# fpa-sao.net
KiCad netlist of a schematic drawn in EAGLE
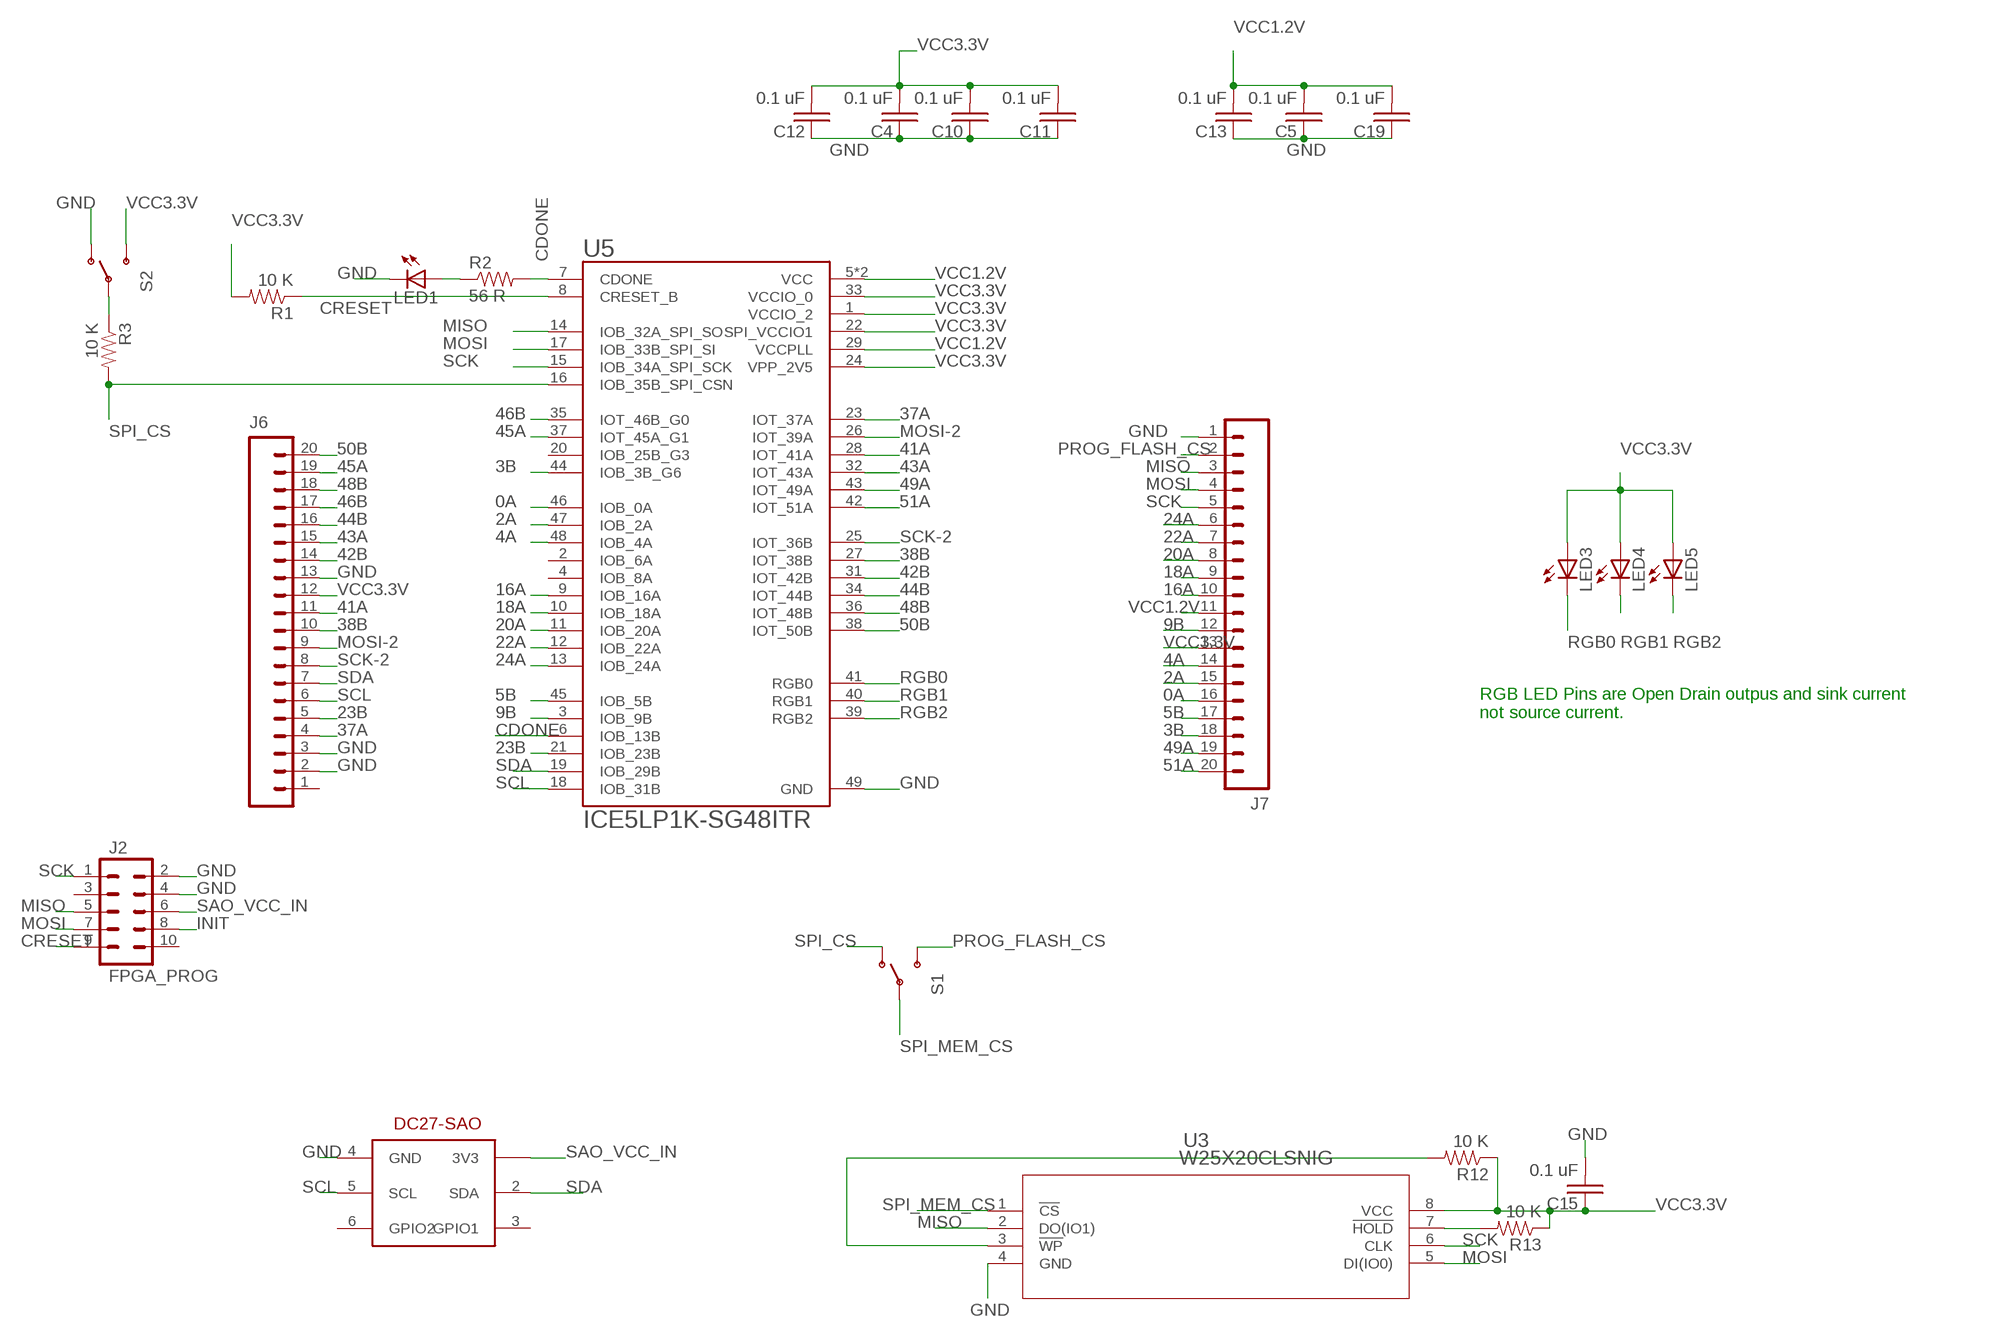
[diagram p0: schematic, sheet 1]
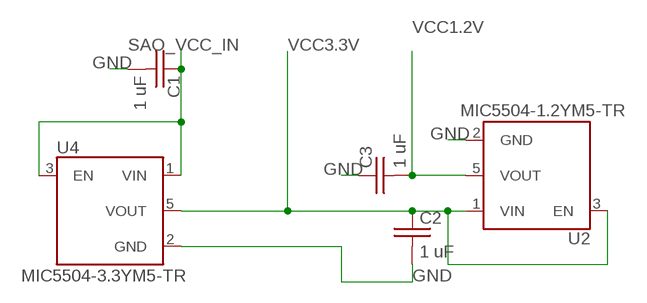
[diagram p1: schematic, sheet 2]
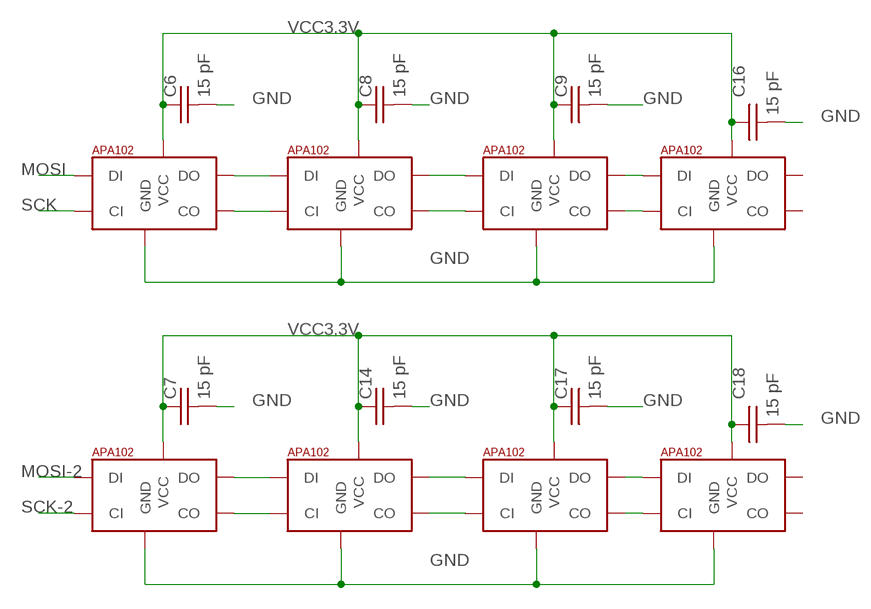
[diagram p2: schematic, sheet 3]
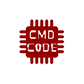
[diagram p3: schematic, sheet 4]

(export (version "E")
  (design (tool "Eeschema 10.0.6"))
  (components
    (comp (ref "C6")
      (value "15 pF")
      (footprint "eagle-import:C1206")
      (libsource (lib "eagle-import") (part "C-USC1206"))
    )
    (comp (ref "C7")
      (value "15 pF")
      (footprint "eagle-import:C1206")
      (libsource (lib "eagle-import") (part "C-USC1206"))
    )
    (comp (ref "C8")
      (value "15 pF")
      (footprint "eagle-import:C1206")
      (libsource (lib "eagle-import") (part "C-USC1206"))
    )
    (comp (ref "C9")
      (value "15 pF")
      (footprint "eagle-import:C1206")
      (libsource (lib "eagle-import") (part "C-USC1206"))
    )
    (comp (ref "C14")
      (value "15 pF")
      (footprint "eagle-import:C1206")
      (libsource (lib "eagle-import") (part "C-USC1206"))
    )
    (comp (ref "C16")
      (value "15 pF")
      (footprint "eagle-import:C1206")
      (libsource (lib "eagle-import") (part "C-USC1206"))
    )
    (comp (ref "C17")
      (value "15 pF")
      (footprint "eagle-import:C1206")
      (libsource (lib "eagle-import") (part "C-USC1206"))
    )
    (comp (ref "C18")
      (value "15 pF")
      (footprint "eagle-import:C1206")
      (libsource (lib "eagle-import") (part "C-USC1206"))
    )
    (comp (ref "U$2")
      (value "APA1025050")
      (footprint "eagle-import:APA102_5050")
      (libsource (lib "eagle-import") (part "APA1025050"))
    )
    (comp (ref "U$3")
      (value "APA1025050")
      (footprint "eagle-import:APA102_5050")
      (libsource (lib "eagle-import") (part "APA1025050"))
    )
    (comp (ref "U$4")
      (value "APA1025050")
      (footprint "eagle-import:APA102_5050")
      (libsource (lib "eagle-import") (part "APA1025050"))
    )
    (comp (ref "U$5")
      (value "APA1025050")
      (footprint "eagle-import:APA102_5050")
      (libsource (lib "eagle-import") (part "APA1025050"))
    )
    (comp (ref "U$6")
      (value "APA1025050")
      (footprint "eagle-import:APA102_5050")
      (libsource (lib "eagle-import") (part "APA1025050"))
    )
    (comp (ref "U$7")
      (value "APA1025050")
      (footprint "eagle-import:APA102_5050")
      (libsource (lib "eagle-import") (part "APA1025050"))
    )
    (comp (ref "U$8")
      (value "APA1025050")
      (footprint "eagle-import:APA102_5050")
      (libsource (lib "eagle-import") (part "APA1025050"))
    )
    (comp (ref "U$10")
      (value "APA1025050")
      (footprint "eagle-import:APA102_5050")
      (libsource (lib "eagle-import") (part "APA1025050"))
    )
    (comp (ref "C4")
      (value "0.1 uF")
      (footprint "eagle-import:C0603")
      (libsource (lib "eagle-import") (part "C-USC0603"))
    )
    (comp (ref "C5")
      (value "0.1 uF")
      (footprint "eagle-import:C0603")
      (libsource (lib "eagle-import") (part "C-USC0603"))
    )
    (comp (ref "C10")
      (value "0.1 uF")
      (footprint "eagle-import:C0603")
      (libsource (lib "eagle-import") (part "C-USC0603"))
    )
    (comp (ref "C11")
      (value "0.1 uF")
      (footprint "eagle-import:C0603")
      (libsource (lib "eagle-import") (part "C-USC0603"))
    )
    (comp (ref "C12")
      (value "0.1 uF")
      (footprint "eagle-import:C0603")
      (libsource (lib "eagle-import") (part "C-USC0603"))
    )
    (comp (ref "C13")
      (value "0.1 uF")
      (footprint "eagle-import:C0603")
      (libsource (lib "eagle-import") (part "C-USC0603"))
    )
    (comp (ref "C15")
      (value "0.1 uF")
      (footprint "eagle-import:C0603")
      (libsource (lib "eagle-import") (part "C-USC0603"))
    )
    (comp (ref "C19")
      (value "0.1 uF")
      (footprint "eagle-import:C0603")
      (libsource (lib "eagle-import") (part "C-USC0603"))
    )
    (comp (ref "J2")
      (value "FPGA_PROG")
      (footprint "eagle-import:2X5_NOSILK")
      (libsource (lib "eagle-import") (part "M05X2NO_SILK"))
    )
    (comp (ref "J6")
      (value "M20NO_SILK_KIT")
      (footprint "eagle-import:1X20_NO_SILK_KIT")
      (libsource (lib "eagle-import") (part "M20NO_SILK_KIT"))
    )
    (comp (ref "J7")
      (value "M20NO_SILK_KIT")
      (footprint "eagle-import:1X20_NO_SILK_KIT")
      (libsource (lib "eagle-import") (part "M20NO_SILK_KIT"))
    )
    (comp (ref "LED1")
      (value "LED1206")
      (footprint "eagle-import:LED-1206")
      (libsource (lib "eagle-import") (part "LED1206"))
    )
    (comp (ref "LED3")
      (value "LED3MM")
      (footprint "eagle-import:LED3MM")
      (libsource (lib "eagle-import") (part "LED3MM"))
    )
    (comp (ref "LED4")
      (value "LED3MM")
      (footprint "eagle-import:LED3MM")
      (libsource (lib "eagle-import") (part "LED3MM"))
    )
    (comp (ref "LED5")
      (value "LED3MM")
      (footprint "eagle-import:LED3MM")
      (libsource (lib "eagle-import") (part "LED3MM"))
    )
    (comp (ref "R1")
      (value "10 K")
      (footprint "eagle-import:0805")
      (libsource (lib "eagle-import") (part "RESISTOR0805-RES"))
    )
    (comp (ref "R2")
      (value "56 R")
      (footprint "eagle-import:1206")
      (libsource (lib "eagle-import") (part "RESISTOR1206"))
    )
    (comp (ref "R3")
      (value "10 K")
      (footprint "eagle-import:0805")
      (libsource (lib "eagle-import") (part "RESISTOR0805-RES"))
    )
    (comp (ref "R12")
      (value "10 K")
      (footprint "eagle-import:0805")
      (libsource (lib "eagle-import") (part "RESISTOR0805-RES"))
    )
    (comp (ref "R13")
      (value "10 K")
      (footprint "eagle-import:0805")
      (libsource (lib "eagle-import") (part "RESISTOR0805-RES"))
    )
    (comp (ref "S1")
      (value "SWITCH-SPSTKIT")
      (footprint "eagle-import:SWITCH-SPDT_KIT")
      (libsource (lib "eagle-import") (part "SWITCH-SPSTKIT"))
    )
    (comp (ref "S2")
      (value "SWITCH-SPSTKIT")
      (footprint "eagle-import:SWITCH-SPDT_KIT")
      (libsource (lib "eagle-import") (part "SWITCH-SPSTKIT"))
    )
    (comp (ref "U$1")
      (value "DC-27-SAO")
      (footprint "eagle-import:3X2")
      (libsource (lib "eagle-import") (part "DC-27-SAO"))
    )
    (comp (ref "U3")
      (value "W25X20CLSNIG")
      (footprint "eagle-import:WIN_SN-8")
      (libsource (lib "eagle-import") (part "W25X20CLSNIG"))
    )
    (comp (ref "U5")
      (value "ICE5LP1K-SG48ITR")
      (footprint "eagle-import:QFN50P700X700X100-49N")
      (fields
        (field (name "DIGI-KEY_PART_NUMBER") "220-2155-1-ND")
        (field (name "MF") "Lattice Semiconductor")
      )
      (libsource (lib "eagle-import") (part "ICE5LP1K-SG48ITR"))
    )
    (comp (ref "U$9")
      (value "CMD_C0DE_LOGOCMD_CODE_LOGO_SILK")
      (footprint "eagle-import:CMD_C0DE_LOGO_SILK")
      (libsource (lib "eagle-import") (part "CMD_C0DE_LOGOCMD_CODE_LOGO_SILK"))
    )
    (comp (ref "C1")
      (value "1 uF")
      (footprint "eagle-import:C0603")
      (libsource (lib "eagle-import") (part "C-USC0603"))
    )
    (comp (ref "C2")
      (value "1 uF")
      (footprint "eagle-import:C0603")
      (libsource (lib "eagle-import") (part "C-USC0603"))
    )
    (comp (ref "C3")
      (value "1 uF")
      (footprint "eagle-import:C0603")
      (libsource (lib "eagle-import") (part "C-USC0603"))
    )
    (comp (ref "U2")
      (value "MIC5504-1.2YM5-TR")
      (footprint "eagle-import:SOT23-5P95_280X145XL45X37N")
      (fields (field (name "MF") "Microchip"))
      (libsource (lib "eagle-import") (part "MIC5504-1.2YM5-TR"))
    )
    (comp (ref "U4")
      (value "MIC5504-3.3YM5-TR")
      (footprint "eagle-import:SOT23-5P95_280X145XL45X37N")
      (fields (field (name "MF") "Microchip") (field (name "MP") "MIC5504-1.2YM5-TR"))
      (libsource (lib "eagle-import") (part "MIC5504-3.3YM5-TR"))
    )
  )
  (nets
    (net (code "1") (name "0A") (class "Default")
      (node (ref "J7") (pin "16") (pinfunction "16_16") (pintype "passive"))
      (node (ref "U5") (pin "46") (pinfunction "IOB_0A_46") (pintype "bidirectional"))
    )
    (net (code "2") (name "2A") (class "Default")
      (node (ref "J7") (pin "15") (pinfunction "15_15") (pintype "passive"))
      (node (ref "U5") (pin "47") (pinfunction "IOB_2A_47") (pintype "bidirectional"))
    )
    (net (code "3") (name "3B") (class "Default")
      (node (ref "J7") (pin "18") (pinfunction "18_18") (pintype "passive"))
      (node (ref "U5") (pin "44") (pinfunction "IOB_3B_G6_44") (pintype "bidirectional"))
    )
    (net (code "4") (name "4A") (class "Default")
      (node (ref "J7") (pin "14") (pinfunction "14_14") (pintype "passive"))
      (node (ref "U5") (pin "48") (pinfunction "IOB_4A_48") (pintype "bidirectional"))
    )
    (net (code "5") (name "5B") (class "Default")
      (node (ref "J7") (pin "17") (pinfunction "17_17") (pintype "passive"))
      (node (ref "U5") (pin "45") (pinfunction "IOB_5B_45") (pintype "bidirectional"))
    )
    (net (code "6") (name "9B") (class "Default")
      (node (ref "J7") (pin "12") (pinfunction "12_12") (pintype "passive"))
      (node (ref "U5") (pin "3") (pinfunction "IOB_9B_3") (pintype "bidirectional"))
    )
    (net (code "7") (name "16A") (class "Default")
      (node (ref "J7") (pin "10") (pinfunction "10_10") (pintype "passive"))
      (node (ref "U5") (pin "9") (pinfunction "IOB_16A_9") (pintype "bidirectional"))
    )
    (net (code "8") (name "18A") (class "Default")
      (node (ref "J7") (pin "9") (pinfunction "9_9") (pintype "passive"))
      (node (ref "U5") (pin "10") (pinfunction "IOB_18A_10") (pintype "bidirectional"))
    )
    (net (code "9") (name "20A") (class "Default")
      (node (ref "J7") (pin "8") (pinfunction "8_8") (pintype "passive"))
      (node (ref "U5") (pin "11") (pinfunction "IOB_20A_11") (pintype "bidirectional"))
    )
    (net (code "10") (name "22A") (class "Default")
      (node (ref "J7") (pin "7") (pinfunction "7_7") (pintype "passive"))
      (node (ref "U5") (pin "12") (pinfunction "IOB_22A_12") (pintype "bidirectional"))
    )
    (net (code "11") (name "23B") (class "Default")
      (node (ref "J6") (pin "5") (pinfunction "5_5") (pintype "passive"))
      (node (ref "U5") (pin "21") (pinfunction "IOB_23B_21") (pintype "bidirectional"))
    )
    (net (code "12") (name "24A") (class "Default")
      (node (ref "J7") (pin "6") (pinfunction "6_6") (pintype "passive"))
      (node (ref "U5") (pin "13") (pinfunction "IOB_24A_13") (pintype "bidirectional"))
    )
    (net (code "13") (name "37A") (class "Default")
      (node (ref "J6") (pin "4") (pinfunction "4_4") (pintype "passive"))
      (node (ref "U5") (pin "23") (pinfunction "IOT_37A_23") (pintype "bidirectional"))
    )
    (net (code "14") (name "38B") (class "Default")
      (node (ref "J6") (pin "10") (pinfunction "10_10") (pintype "passive"))
      (node (ref "U5") (pin "27") (pinfunction "IOT_38B_27") (pintype "bidirectional"))
    )
    (net (code "15") (name "41A") (class "Default")
      (node (ref "J6") (pin "11") (pinfunction "11_11") (pintype "passive"))
      (node (ref "U5") (pin "28") (pinfunction "IOT_41A_28") (pintype "bidirectional"))
    )
    (net (code "16") (name "42B") (class "Default")
      (node (ref "J6") (pin "14") (pinfunction "14_14") (pintype "passive"))
      (node (ref "U5") (pin "31") (pinfunction "IOT_42B_31") (pintype "bidirectional"))
    )
    (net (code "17") (name "43A") (class "Default")
      (node (ref "J6") (pin "15") (pinfunction "15_15") (pintype "passive"))
      (node (ref "U5") (pin "32") (pinfunction "IOT_43A_32") (pintype "bidirectional"))
    )
    (net (code "18") (name "44B") (class "Default")
      (node (ref "J6") (pin "16") (pinfunction "16_16") (pintype "passive"))
      (node (ref "U5") (pin "34") (pinfunction "IOT_44B_34") (pintype "bidirectional"))
    )
    (net (code "19") (name "45A") (class "Default")
      (node (ref "J6") (pin "19") (pinfunction "19_19") (pintype "passive"))
      (node (ref "U5") (pin "37") (pinfunction "IOT_45A_G1_37") (pintype "bidirectional"))
    )
    (net (code "20") (name "46B") (class "Default")
      (node (ref "J6") (pin "17") (pinfunction "17_17") (pintype "passive"))
      (node (ref "U5") (pin "35") (pinfunction "IOT_46B_G0_35") (pintype "bidirectional"))
    )
    (net (code "21") (name "48B") (class "Default")
      (node (ref "J6") (pin "18") (pinfunction "18_18") (pintype "passive"))
      (node (ref "U5") (pin "36") (pinfunction "IOT_48B_36") (pintype "bidirectional"))
    )
    (net (code "22") (name "49A") (class "Default")
      (node (ref "J7") (pin "19") (pinfunction "19_19") (pintype "passive"))
      (node (ref "U5") (pin "43") (pinfunction "IOT_49A_43") (pintype "bidirectional"))
    )
    (net (code "23") (name "50B") (class "Default")
      (node (ref "J6") (pin "20") (pinfunction "20_20") (pintype "passive"))
      (node (ref "U5") (pin "38") (pinfunction "IOT_50B_38") (pintype "bidirectional"))
    )
    (net (code "24") (name "51A") (class "Default")
      (node (ref "J7") (pin "20") (pinfunction "20_20") (pintype "passive"))
      (node (ref "U5") (pin "42") (pinfunction "IOT_51A_42") (pintype "bidirectional"))
    )
    (net (code "25") (name "CDONE") (class "Default")
      (node (ref "R2") (pin "2") (pinfunction "2_2") (pintype "passive"))
      (node (ref "U5") (pin "6") (pinfunction "IOB_13B_6") (pintype "bidirectional"))
      (node (ref "U5") (pin "7") (pinfunction "CDONE_7") (pintype "input"))
    )
    (net (code "26") (name "CRESET") (class "Default")
      (node (ref "J2") (pin "9") (pinfunction "9_9") (pintype "passive"))
      (node (ref "R1") (pin "1") (pinfunction "1_1") (pintype "passive"))
      (node (ref "U5") (pin "8") (pinfunction "CRESET_B_8") (pintype "input"))
    )
    (net (code "27") (name "GND") (class "Default")
      (node (ref "C1") (pin "2") (pinfunction "2_2") (pintype "passive"))
      (node (ref "C10") (pin "1") (pinfunction "1_1") (pintype "passive"))
      (node (ref "C11") (pin "1") (pinfunction "1_1") (pintype "passive"))
      (node (ref "C12") (pin "1") (pinfunction "1_1") (pintype "passive"))
      (node (ref "C13") (pin "1") (pinfunction "1_1") (pintype "passive"))
      (node (ref "C14") (pin "2") (pinfunction "2_2") (pintype "passive"))
      (node (ref "C15") (pin "2") (pinfunction "2_2") (pintype "passive"))
      (node (ref "C16") (pin "2") (pinfunction "2_2") (pintype "passive"))
      (node (ref "C17") (pin "2") (pinfunction "2_2") (pintype "passive"))
      (node (ref "C18") (pin "2") (pinfunction "2_2") (pintype "passive"))
      (node (ref "C19") (pin "1") (pinfunction "1_1") (pintype "passive"))
      (node (ref "C2") (pin "2") (pinfunction "2_2") (pintype "passive"))
      (node (ref "C3") (pin "1") (pinfunction "1_1") (pintype "passive"))
      (node (ref "C4") (pin "1") (pinfunction "1_1") (pintype "passive"))
      (node (ref "C5") (pin "1") (pinfunction "1_1") (pintype "passive"))
      (node (ref "C6") (pin "2") (pinfunction "2_2") (pintype "passive"))
      (node (ref "C7") (pin "2") (pinfunction "2_2") (pintype "passive"))
      (node (ref "C8") (pin "2") (pinfunction "2_2") (pintype "passive"))
      (node (ref "C9") (pin "2") (pinfunction "2_2") (pintype "passive"))
      (node (ref "J2") (pin "2") (pinfunction "2_2") (pintype "passive"))
      (node (ref "J2") (pin "4") (pinfunction "4_4") (pintype "passive"))
      (node (ref "J6") (pin "13") (pinfunction "13_13") (pintype "passive"))
      (node (ref "J6") (pin "2") (pinfunction "2_2") (pintype "passive"))
      (node (ref "J6") (pin "3") (pinfunction "3_3") (pintype "passive"))
      (node (ref "J7") (pin "1") (pinfunction "1_1") (pintype "passive"))
      (node (ref "LED1") (pin "C") (pinfunction "C_C") (pintype "output"))
      (node (ref "S2") (pin "1") (pinfunction "O_1") (pintype "passive"))
      (node (ref "U$1") (pin "4") (pinfunction "GND_4") (pintype "power_in"))
      (node (ref "U$10") (pin "6") (pinfunction "GND_6") (pintype "bidirectional"))
      (node (ref "U$2") (pin "6") (pinfunction "GND_6") (pintype "bidirectional"))
      (node (ref "U$3") (pin "6") (pinfunction "GND_6") (pintype "bidirectional"))
      (node (ref "U$4") (pin "6") (pinfunction "GND_6") (pintype "bidirectional"))
      (node (ref "U$5") (pin "6") (pinfunction "GND_6") (pintype "bidirectional"))
      (node (ref "U$6") (pin "6") (pinfunction "GND_6") (pintype "bidirectional"))
      (node (ref "U$7") (pin "6") (pinfunction "GND_6") (pintype "bidirectional"))
      (node (ref "U$8") (pin "6") (pinfunction "GND_6") (pintype "bidirectional"))
      (node (ref "U2") (pin "2") (pinfunction "GND_2") (pintype "power_in"))
      (node (ref "U3") (pin "4") (pinfunction "GND_4") (pintype "power_in"))
      (node (ref "U4") (pin "2") (pinfunction "GND_2") (pintype "power_in"))
      (node (ref "U5") (pin "49") (pinfunction "GND_49") (pintype "power_in"))
    )
    (net (code "28") (name "INIT") (class "Default")
      (node (ref "J2") (pin "8") (pinfunction "8_8") (pintype "passive"))
    )
    (net (code "29") (name "MISO") (class "Default")
      (node (ref "J2") (pin "5") (pinfunction "5_5") (pintype "passive"))
      (node (ref "J7") (pin "3") (pinfunction "3_3") (pintype "passive"))
      (node (ref "U3") (pin "2") (pinfunction "DO(IO1)_2") (pintype "bidirectional"))
      (node (ref "U5") (pin "14") (pinfunction "IOB_32A_SPI_SO_14") (pintype "bidirectional"))
    )
    (net (code "30") (name "MOSI") (class "Default")
      (node (ref "J2") (pin "7") (pinfunction "7_7") (pintype "passive"))
      (node (ref "J7") (pin "4") (pinfunction "4_4") (pintype "passive"))
      (node (ref "U$6") (pin "4") (pinfunction "DI_4") (pintype "bidirectional"))
      (node (ref "U3") (pin "5") (pinfunction "DI(IO0)_5") (pintype "bidirectional"))
      (node (ref "U5") (pin "17") (pinfunction "IOB_33B_SPI_SI_17") (pintype "bidirectional"))
    )
    (net (code "31") (name "MOSI-2") (class "Default")
      (node (ref "J6") (pin "9") (pinfunction "9_9") (pintype "passive"))
      (node (ref "U$2") (pin "4") (pinfunction "DI_4") (pintype "bidirectional"))
      (node (ref "U5") (pin "26") (pinfunction "IOT_39A_26") (pintype "bidirectional"))
    )
    (net (code "32") (name "Net-(LED1-PadA)") (class "Default")
      (node (ref "LED1") (pin "A") (pinfunction "A_A") (pintype "input"))
      (node (ref "R2") (pin "1") (pinfunction "1_1") (pintype "passive"))
    )
    (net (code "33") (name "Net-(S2-P)") (class "Default")
      (node (ref "R3") (pin "1") (pinfunction "1_1") (pintype "passive"))
      (node (ref "S2") (pin "2") (pinfunction "P_2") (pintype "passive"))
    )
    (net (code "34") (name "Net-(U$2-CO)") (class "Default")
      (node (ref "U$2") (pin "2") (pinfunction "CO_2") (pintype "bidirectional"))
      (node (ref "U$3") (pin "5") (pinfunction "CI_5") (pintype "bidirectional"))
    )
    (net (code "35") (name "Net-(U$2-DO)") (class "Default")
      (node (ref "U$2") (pin "3") (pinfunction "DO_3") (pintype "bidirectional"))
      (node (ref "U$3") (pin "4") (pinfunction "DI_4") (pintype "bidirectional"))
    )
    (net (code "36") (name "Net-(U$3-CO)") (class "Default")
      (node (ref "U$3") (pin "2") (pinfunction "CO_2") (pintype "bidirectional"))
      (node (ref "U$4") (pin "5") (pinfunction "CI_5") (pintype "bidirectional"))
    )
    (net (code "37") (name "Net-(U$3-DO)") (class "Default")
      (node (ref "U$3") (pin "3") (pinfunction "DO_3") (pintype "bidirectional"))
      (node (ref "U$4") (pin "4") (pinfunction "DI_4") (pintype "bidirectional"))
    )
    (net (code "38") (name "Net-(U$4-CO)") (class "Default")
      (node (ref "U$4") (pin "2") (pinfunction "CO_2") (pintype "bidirectional"))
      (node (ref "U$5") (pin "5") (pinfunction "CI_5") (pintype "bidirectional"))
    )
    (net (code "39") (name "Net-(U$4-DO)") (class "Default")
      (node (ref "U$4") (pin "3") (pinfunction "DO_3") (pintype "bidirectional"))
      (node (ref "U$5") (pin "4") (pinfunction "DI_4") (pintype "bidirectional"))
    )
    (net (code "40") (name "Net-(U$6-CO)") (class "Default")
      (node (ref "U$6") (pin "2") (pinfunction "CO_2") (pintype "bidirectional"))
      (node (ref "U$7") (pin "5") (pinfunction "CI_5") (pintype "bidirectional"))
    )
    (net (code "41") (name "Net-(U$6-DO)") (class "Default")
      (node (ref "U$6") (pin "3") (pinfunction "DO_3") (pintype "bidirectional"))
      (node (ref "U$7") (pin "4") (pinfunction "DI_4") (pintype "bidirectional"))
    )
    (net (code "42") (name "Net-(U$7-CO)") (class "Default")
      (node (ref "U$7") (pin "2") (pinfunction "CO_2") (pintype "bidirectional"))
      (node (ref "U$8") (pin "5") (pinfunction "CI_5") (pintype "bidirectional"))
    )
    (net (code "43") (name "Net-(U$7-DO)") (class "Default")
      (node (ref "U$7") (pin "3") (pinfunction "DO_3") (pintype "bidirectional"))
      (node (ref "U$8") (pin "4") (pinfunction "DI_4") (pintype "bidirectional"))
    )
    (net (code "44") (name "Net-(U$10-CI)") (class "Default")
      (node (ref "U$10") (pin "5") (pinfunction "CI_5") (pintype "bidirectional"))
      (node (ref "U$8") (pin "2") (pinfunction "CO_2") (pintype "bidirectional"))
    )
    (net (code "45") (name "Net-(U$10-DI)") (class "Default")
      (node (ref "U$10") (pin "4") (pinfunction "DI_4") (pintype "bidirectional"))
      (node (ref "U$8") (pin "3") (pinfunction "DO_3") (pintype "bidirectional"))
    )
    (net (code "46") (name "Net-(U3-~{HOLD})") (class "Default")
      (node (ref "R13") (pin "2") (pinfunction "2_2") (pintype "passive"))
      (node (ref "U3") (pin "7") (pinfunction "~{HOLD}_7") (pintype "input"))
    )
    (net (code "47") (name "Net-(U3-~{WP})") (class "Default")
      (node (ref "R12") (pin "2") (pinfunction "2_2") (pintype "passive"))
      (node (ref "U3") (pin "3") (pinfunction "~{WP}_3") (pintype "input"))
    )
    (net (code "48") (name "PROG_FLASH_CS") (class "Default")
      (node (ref "J7") (pin "2") (pinfunction "2_2") (pintype "passive"))
      (node (ref "S1") (pin "3") (pinfunction "S_3") (pintype "passive"))
    )
    (net (code "49") (name "RGB0") (class "Default")
      (node (ref "LED3") (pin "K") (pinfunction "C_K") (pintype "output"))
      (node (ref "U5") (pin "41") (pinfunction "RGB0_41") (pintype "passive"))
    )
    (net (code "50") (name "RGB1") (class "Default")
      (node (ref "LED4") (pin "K") (pinfunction "C_K") (pintype "output"))
      (node (ref "U5") (pin "40") (pinfunction "RGB1_40") (pintype "passive"))
    )
    (net (code "51") (name "RGB2") (class "Default")
      (node (ref "LED5") (pin "K") (pinfunction "C_K") (pintype "output"))
      (node (ref "U5") (pin "39") (pinfunction "RGB2_39") (pintype "passive"))
    )
    (net (code "52") (name "SAO_VCC_IN") (class "Default")
      (node (ref "C1") (pin "1") (pinfunction "1_1") (pintype "passive"))
      (node (ref "J2") (pin "6") (pinfunction "6_6") (pintype "passive"))
      (node (ref "U$1") (pin "1") (pinfunction "3V3_1") (pintype "power_in"))
      (node (ref "U4") (pin "1") (pinfunction "VIN_1") (pintype "power_in"))
      (node (ref "U4") (pin "3") (pinfunction "EN_3") (pintype "input"))
    )
    (net (code "53") (name "SCK") (class "Default")
      (node (ref "J2") (pin "1") (pinfunction "1_1") (pintype "passive"))
      (node (ref "J7") (pin "5") (pinfunction "5_5") (pintype "passive"))
      (node (ref "U$6") (pin "5") (pinfunction "CI_5") (pintype "bidirectional"))
      (node (ref "U3") (pin "6") (pinfunction "CLK_6") (pintype "input"))
      (node (ref "U5") (pin "15") (pinfunction "IOB_34A_SPI_SCK_15") (pintype "bidirectional"))
    )
    (net (code "54") (name "SCK-2") (class "Default")
      (node (ref "J6") (pin "8") (pinfunction "8_8") (pintype "passive"))
      (node (ref "U$2") (pin "5") (pinfunction "CI_5") (pintype "bidirectional"))
      (node (ref "U5") (pin "25") (pinfunction "IOT_36B_25") (pintype "bidirectional"))
    )
    (net (code "55") (name "SCL") (class "Default")
      (node (ref "J6") (pin "6") (pinfunction "6_6") (pintype "passive"))
      (node (ref "U$1") (pin "5") (pinfunction "SCL_5") (pintype "bidirectional"))
      (node (ref "U5") (pin "18") (pinfunction "IOB_31B_18") (pintype "bidirectional"))
    )
    (net (code "56") (name "SDA") (class "Default")
      (node (ref "J6") (pin "7") (pinfunction "7_7") (pintype "passive"))
      (node (ref "U$1") (pin "2") (pinfunction "SDA_2") (pintype "bidirectional"))
      (node (ref "U5") (pin "19") (pinfunction "IOB_29B_19") (pintype "bidirectional"))
    )
    (net (code "57") (name "SPI_CS") (class "Default")
      (node (ref "R3") (pin "2") (pinfunction "2_2") (pintype "passive"))
      (node (ref "S1") (pin "1") (pinfunction "O_1") (pintype "passive"))
      (node (ref "U5") (pin "16") (pinfunction "IOB_35B_SPI_CSN_16") (pintype "bidirectional"))
    )
    (net (code "58") (name "SPI_MEM_CS") (class "Default")
      (node (ref "S1") (pin "2") (pinfunction "P_2") (pintype "passive"))
      (node (ref "U3") (pin "1") (pinfunction "~{CS}_1") (pintype "input"))
    )
    (net (code "59") (name "VCC1.2V") (class "Default")
      (node (ref "C13") (pin "2") (pinfunction "2_2") (pintype "passive"))
      (node (ref "C19") (pin "2") (pinfunction "2_2") (pintype "passive"))
      (node (ref "C3") (pin "2") (pinfunction "2_2") (pintype "passive"))
      (node (ref "C5") (pin "2") (pinfunction "2_2") (pintype "passive"))
      (node (ref "J7") (pin "11") (pinfunction "11_11") (pintype "passive"))
      (node (ref "U2") (pin "5") (pinfunction "VOUT_5") (pintype "output"))
      (node (ref "U5") (pin "29") (pinfunction "VCCPLL_29") (pintype "power_in"))
      (node (ref "U5") (pin "30") (pinfunction "VCC_30") (pintype "power_in"))
      (node (ref "U5") (pin "5") (pinfunction "VCC_5") (pintype "power_in"))
    )
    (net (code "60") (name "VCC3.3V") (class "Default")
      (node (ref "C10") (pin "2") (pinfunction "2_2") (pintype "passive"))
      (node (ref "C11") (pin "2") (pinfunction "2_2") (pintype "passive"))
      (node (ref "C12") (pin "2") (pinfunction "2_2") (pintype "passive"))
      (node (ref "C14") (pin "1") (pinfunction "1_1") (pintype "passive"))
      (node (ref "C15") (pin "1") (pinfunction "1_1") (pintype "passive"))
      (node (ref "C16") (pin "1") (pinfunction "1_1") (pintype "passive"))
      (node (ref "C17") (pin "1") (pinfunction "1_1") (pintype "passive"))
      (node (ref "C18") (pin "1") (pinfunction "1_1") (pintype "passive"))
      (node (ref "C2") (pin "1") (pinfunction "1_1") (pintype "passive"))
      (node (ref "C4") (pin "2") (pinfunction "2_2") (pintype "passive"))
      (node (ref "C6") (pin "1") (pinfunction "1_1") (pintype "passive"))
      (node (ref "C7") (pin "1") (pinfunction "1_1") (pintype "passive"))
      (node (ref "C8") (pin "1") (pinfunction "1_1") (pintype "passive"))
      (node (ref "C9") (pin "1") (pinfunction "1_1") (pintype "passive"))
      (node (ref "J6") (pin "12") (pinfunction "12_12") (pintype "passive"))
      (node (ref "J7") (pin "13") (pinfunction "13_13") (pintype "passive"))
      (node (ref "LED3") (pin "A") (pinfunction "A_A") (pintype "input"))
      (node (ref "LED4") (pin "A") (pinfunction "A_A") (pintype "input"))
      (node (ref "LED5") (pin "A") (pinfunction "A_A") (pintype "input"))
      (node (ref "R1") (pin "2") (pinfunction "2_2") (pintype "passive"))
      (node (ref "R12") (pin "1") (pinfunction "1_1") (pintype "passive"))
      (node (ref "R13") (pin "1") (pinfunction "1_1") (pintype "passive"))
      (node (ref "S2") (pin "3") (pinfunction "S_3") (pintype "passive"))
      (node (ref "U$10") (pin "1") (pinfunction "VCC_1") (pintype "bidirectional"))
      (node (ref "U$2") (pin "1") (pinfunction "VCC_1") (pintype "bidirectional"))
      (node (ref "U$3") (pin "1") (pinfunction "VCC_1") (pintype "bidirectional"))
      (node (ref "U$4") (pin "1") (pinfunction "VCC_1") (pintype "bidirectional"))
      (node (ref "U$5") (pin "1") (pinfunction "VCC_1") (pintype "bidirectional"))
      (node (ref "U$6") (pin "1") (pinfunction "VCC_1") (pintype "bidirectional"))
      (node (ref "U$7") (pin "1") (pinfunction "VCC_1") (pintype "bidirectional"))
      (node (ref "U$8") (pin "1") (pinfunction "VCC_1") (pintype "bidirectional"))
      (node (ref "U2") (pin "1") (pinfunction "VIN_1") (pintype "power_in"))
      (node (ref "U2") (pin "3") (pinfunction "EN_3") (pintype "input"))
      (node (ref "U3") (pin "8") (pinfunction "VCC_8") (pintype "power_in"))
      (node (ref "U4") (pin "5") (pinfunction "VOUT_5") (pintype "output"))
      (node (ref "U5") (pin "1") (pinfunction "VCCIO_2_1") (pintype "power_in"))
      (node (ref "U5") (pin "22") (pinfunction "SPI_VCCIO1_22") (pintype "power_in"))
      (node (ref "U5") (pin "24") (pinfunction "VPP_2V5_24") (pintype "power_in"))
      (node (ref "U5") (pin "33") (pinfunction "VCCIO_0_33") (pintype "power_in"))
    )
    (net (code "61") (name "unconnected-(J2-Pad3)") (class "Default")
      (node (ref "J2") (pin "3") (pinfunction "3_3") (pintype "passive"))
    )
    (net (code "62") (name "unconnected-(J2-Pad10)") (class "Default")
      (node (ref "J2") (pin "10") (pinfunction "10_10") (pintype "passive"))
    )
    (net (code "63") (name "unconnected-(J6-Pad1)") (class "Default")
      (node (ref "J6") (pin "1") (pinfunction "1_1") (pintype "passive"))
    )
    (net (code "64") (name "unconnected-(U$1-GPIO1-Pad3)") (class "Default")
      (node (ref "U$1") (pin "3") (pinfunction "GPIO1_3") (pintype "bidirectional"))
    )
    (net (code "65") (name "unconnected-(U$1-GPIO2-Pad6)") (class "Default")
      (node (ref "U$1") (pin "6") (pinfunction "GPIO2_6") (pintype "bidirectional"))
    )
    (net (code "66") (name "unconnected-(U$5-CO-Pad2)") (class "Default")
      (node (ref "U$5") (pin "2") (pinfunction "CO_2") (pintype "bidirectional"))
    )
    (net (code "67") (name "unconnected-(U$5-DO-Pad3)") (class "Default")
      (node (ref "U$5") (pin "3") (pinfunction "DO_3") (pintype "bidirectional"))
    )
    (net (code "68") (name "unconnected-(U$10-CO-Pad2)") (class "Default")
      (node (ref "U$10") (pin "2") (pinfunction "CO_2") (pintype "bidirectional"))
    )
    (net (code "69") (name "unconnected-(U$10-DO-Pad3)") (class "Default")
      (node (ref "U$10") (pin "3") (pinfunction "DO_3") (pintype "bidirectional"))
    )
    (net (code "70") (name "unconnected-(U5-IOB_6A-Pad2)") (class "Default")
      (node (ref "U5") (pin "2") (pinfunction "IOB_6A_2") (pintype "bidirectional"))
    )
    (net (code "71") (name "unconnected-(U5-IOB_8A-Pad4)") (class "Default")
      (node (ref "U5") (pin "4") (pinfunction "IOB_8A_4") (pintype "bidirectional"))
    )
    (net (code "72") (name "unconnected-(U5-IOB_25B_G3-Pad20)") (class "Default")
      (node (ref "U5") (pin "20") (pinfunction "IOB_25B_G3_20") (pintype "bidirectional"))
    )
  )
)
